# LDP_DS_V2_0.net
KiCad netlist of a schematic drawn in Altium Designer
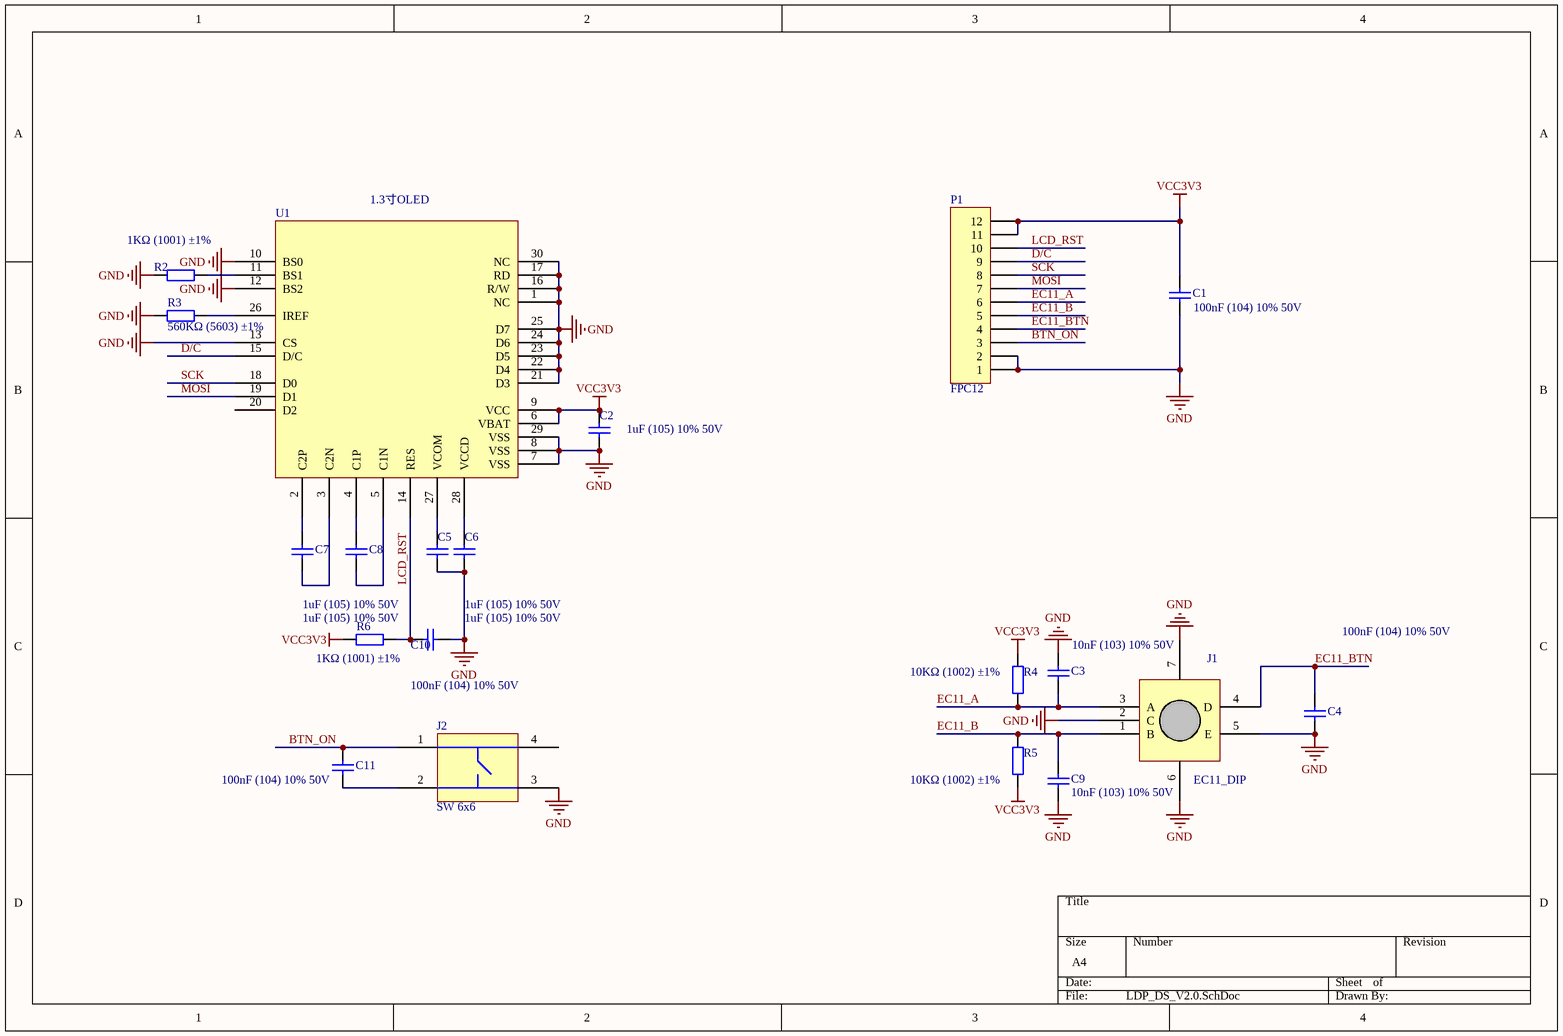
[diagram p0: LDP_DS_V2.0.SchDoc]

(export (version "E")
  (design (tool "Eeschema 10.0.6"))
  (components
    (comp (ref "C1")
      (value "100nF (104) 10% 50V")
      (footprint "0603_C")
      (description "贴片电容")
      (libsource (lib "Cap") (part "0603 100nF (104) 10% 50V"))
    )
    (comp (ref "C2")
      (value "1uF (105) 10% 50V")
      (footprint "0603_C")
      (description "贴片电容")
      (libsource (lib "Cap") (part "0603 1uF (105) 10% 50V"))
    )
    (comp (ref "C3")
      (value "10nF (103) 10% 50V")
      (footprint "0603_C")
      (description "贴片电容")
      (libsource (lib "Cap") (part "0603 10nF (103) 10% 50V"))
    )
    (comp (ref "C4")
      (value "100nF (104) 10% 50V")
      (footprint "0603_C")
      (description "贴片电容")
      (libsource (lib "Cap") (part "0603 100nF (104) 10% 50V"))
    )
    (comp (ref "C5")
      (value "1uF (105) 10% 50V")
      (footprint "0603_C")
      (description "贴片电容")
      (libsource (lib "Cap") (part "0603 1uF (105) 10% 50V"))
    )
    (comp (ref "C6")
      (value "1uF (105) 10% 50V")
      (footprint "0603_C")
      (description "贴片电容")
      (libsource (lib "Cap") (part "0603 1uF (105) 10% 50V"))
    )
    (comp (ref "C7")
      (value "1uF (105) 10% 50V")
      (footprint "0603_C")
      (description "贴片电容")
      (libsource (lib "Cap") (part "0603 1uF (105) 10% 50V"))
    )
    (comp (ref "C8")
      (value "1uF (105) 10% 50V")
      (footprint "0603_C")
      (description "贴片电容")
      (libsource (lib "Cap") (part "0603 1uF (105) 10% 50V"))
    )
    (comp (ref "C9")
      (value "10nF (103) 10% 50V")
      (footprint "0603_C")
      (description "贴片电容")
      (libsource (lib "Cap") (part "0603 10nF (103) 10% 50V"))
    )
    (comp (ref "C10")
      (value "100nF (104) 10% 50V")
      (footprint "0603_C")
      (description "贴片电容")
      (libsource (lib "Cap") (part "0603 100nF (104) 10% 50V"))
    )
    (comp (ref "C11")
      (value "100nF (104) 10% 50V")
      (footprint "0603_C")
      (description "贴片电容")
      (libsource (lib "Cap") (part "0603 100nF (104) 10% 50V"))
    )
    (comp (ref "J1") (value "EC11_DIP") (footprint "EC11_DIP") (libsource (lib "CONNECT") (part "EC11_DIP")))
    (comp (ref "J2") (value "SW 6x6") (footprint "SW 6x6") (libsource (lib "CONNECT") (part "SW 6x6")))
    (comp (ref "P1")
      (value "FPC12")
      (footprint "FPC_12")
      (description "Header, 12-Pin")
      (fields (field (name "PUBLISHER") "Altium Limited"))
      (libsource (lib "Miscellaneous Connectors") (part "Header 12"))
    )
    (comp (ref "R2")
      (value "1KΩ (1001) ±1%")
      (footprint "0603_R")
      (description "贴片电阻")
      (libsource (lib "RES") (part "0603 1KΩ (1001) 1%"))
    )
    (comp (ref "R3")
      (value "560KΩ (5603) ±1%")
      (footprint "0603_R")
      (description "贴片电阻")
      (libsource (lib "RES") (part "0603 560KΩ (5603) 1%"))
    )
    (comp (ref "R4")
      (value "10KΩ (1002) ±1%")
      (footprint "0603_R")
      (description "贴片电阻")
      (libsource (lib "RES") (part "0603 10KΩ (1002) 1%"))
    )
    (comp (ref "R5")
      (value "10KΩ (1002) ±1%")
      (footprint "0603_R")
      (description "贴片电阻")
      (libsource (lib "RES") (part "0603 10KΩ (1002) 1%"))
    )
    (comp (ref "R6")
      (value "1KΩ (1001) ±1%")
      (footprint "0603_R")
      (description "贴片电阻")
      (libsource (lib "RES") (part "0603 1KΩ (1001) 1%"))
    )
    (comp (ref "U1") (value "1.3寸OLED") (footprint "1.3寸OLED") (libsource (lib "LED") (part "1.3寸OLED")))
  )
  (nets
    (net (code "1") (name "/BTN_ON") (class "Default")
      (node (ref "C11") (pin "2") (pinfunction "2_2") (pintype "passive"))
      (node (ref "J2") (pin "1") (pintype "passive"))
      (node (ref "P1") (pin "3") (pinfunction "3_3") (pintype "passive"))
    )
    (net (code "2") (name "/D{slash}C") (class "Default")
      (node (ref "P1") (pin "9") (pinfunction "9_9") (pintype "passive"))
      (node (ref "U1") (pin "15") (pinfunction "D/C_15") (pintype "passive"))
    )
    (net (code "3") (name "/EC11_A") (class "Default")
      (node (ref "C3") (pin "1") (pinfunction "1_1") (pintype "passive"))
      (node (ref "J1") (pin "3") (pinfunction "A_3") (pintype "passive"))
      (node (ref "P1") (pin "6") (pinfunction "6_6") (pintype "passive"))
      (node (ref "R4") (pin "1") (pinfunction "1_1") (pintype "passive"))
    )
    (net (code "4") (name "/EC11_B") (class "Default")
      (node (ref "C9") (pin "2") (pinfunction "2_2") (pintype "passive"))
      (node (ref "J1") (pin "1") (pinfunction "B_1") (pintype "passive"))
      (node (ref "P1") (pin "5") (pinfunction "5_5") (pintype "passive"))
      (node (ref "R5") (pin "2") (pinfunction "2_2") (pintype "passive"))
    )
    (net (code "5") (name "/EC11_BTN") (class "Default")
      (node (ref "C4") (pin "2") (pinfunction "2_2") (pintype "passive"))
      (node (ref "J1") (pin "4") (pinfunction "D_4") (pintype "passive"))
      (node (ref "P1") (pin "4") (pinfunction "4_4") (pintype "passive"))
    )
    (net (code "6") (name "/LCD_RST") (class "Default")
      (node (ref "C10") (pin "1") (pinfunction "1_1") (pintype "passive"))
      (node (ref "P1") (pin "10") (pinfunction "10_10") (pintype "passive"))
      (node (ref "R6") (pin "1") (pinfunction "1_1") (pintype "passive"))
      (node (ref "U1") (pin "14") (pinfunction "RES_14") (pintype "passive"))
    )
    (net (code "7") (name "/MOSI") (class "Default")
      (node (ref "P1") (pin "7") (pinfunction "7_7") (pintype "passive"))
      (node (ref "U1") (pin "19") (pinfunction "D1_19") (pintype "passive"))
    )
    (net (code "8") (name "/SCK") (class "Default")
      (node (ref "P1") (pin "8") (pinfunction "8_8") (pintype "passive"))
      (node (ref "U1") (pin "18") (pinfunction "D0_18") (pintype "passive"))
    )
    (net (code "9") (name "GND") (class "Default")
      (node (ref "C1") (pin "1") (pinfunction "1_1") (pintype "passive"))
      (node (ref "C10") (pin "2") (pinfunction "2_2") (pintype "passive"))
      (node (ref "C2") (pin "1") (pinfunction "1_1") (pintype "passive"))
      (node (ref "C3") (pin "2") (pinfunction "2_2") (pintype "passive"))
      (node (ref "C4") (pin "1") (pinfunction "1_1") (pintype "passive"))
      (node (ref "C5") (pin "1") (pinfunction "1_1") (pintype "passive"))
      (node (ref "C6") (pin "1") (pinfunction "1_1") (pintype "passive"))
      (node (ref "C9") (pin "1") (pinfunction "1_1") (pintype "passive"))
      (node (ref "J1") (pin "2") (pinfunction "C_2") (pintype "passive"))
      (node (ref "J1") (pin "5") (pinfunction "E_5") (pintype "passive"))
      (node (ref "J1") (pin "6") (pintype "passive"))
      (node (ref "J1") (pin "7") (pintype "passive"))
      (node (ref "J2") (pin "3") (pintype "passive"))
      (node (ref "P1") (pin "1") (pinfunction "1_1") (pintype "passive"))
      (node (ref "P1") (pin "2") (pinfunction "2_2") (pintype "passive"))
      (node (ref "R2") (pin "2") (pinfunction "2_2") (pintype "passive"))
      (node (ref "R3") (pin "1") (pinfunction "1_1") (pintype "passive"))
      (node (ref "U1") (pin "1") (pinfunction "NC_1") (pintype "passive"))
      (node (ref "U1") (pin "10") (pinfunction "BS0_10") (pintype "passive"))
      (node (ref "U1") (pin "12") (pinfunction "BS2_12") (pintype "passive"))
      (node (ref "U1") (pin "13") (pinfunction "CS_13") (pintype "passive"))
      (node (ref "U1") (pin "16") (pinfunction "R/W_16") (pintype "passive"))
      (node (ref "U1") (pin "17") (pinfunction "RD_17") (pintype "passive"))
      (node (ref "U1") (pin "21") (pinfunction "D3_21") (pintype "passive"))
      (node (ref "U1") (pin "22") (pinfunction "D4_22") (pintype "passive"))
      (node (ref "U1") (pin "23") (pinfunction "D5_23") (pintype "passive"))
      (node (ref "U1") (pin "24") (pinfunction "D6_24") (pintype "passive"))
      (node (ref "U1") (pin "25") (pinfunction "D7_25") (pintype "passive"))
      (node (ref "U1") (pin "29") (pinfunction "VSS_29") (pintype "passive"))
      (node (ref "U1") (pin "30") (pinfunction "NC_30") (pintype "passive"))
      (node (ref "U1") (pin "7") (pinfunction "VSS_7") (pintype "passive"))
      (node (ref "U1") (pin "8") (pinfunction "VSS_8") (pintype "passive"))
    )
    (net (code "10") (name "Net-(C11-Pad1)") (class "Default")
      (node (ref "C11") (pin "1") (pinfunction "1_1") (pintype "passive"))
      (node (ref "J2") (pin "2") (pintype "passive"))
    )
    (net (code "11") (name "Net-(U1-BS1)") (class "Default")
      (node (ref "R2") (pin "1") (pinfunction "1_1") (pintype "passive"))
      (node (ref "U1") (pin "11") (pinfunction "BS1_11") (pintype "passive"))
    )
    (net (code "12") (name "Net-(U1-C1N)") (class "Default")
      (node (ref "C8") (pin "1") (pinfunction "1_1") (pintype "passive"))
      (node (ref "U1") (pin "5") (pinfunction "C1N_5") (pintype "passive"))
    )
    (net (code "13") (name "Net-(U1-C1P)") (class "Default")
      (node (ref "C8") (pin "2") (pinfunction "2_2") (pintype "passive"))
      (node (ref "U1") (pin "4") (pinfunction "C1P_4") (pintype "passive"))
    )
    (net (code "14") (name "Net-(U1-C2N)") (class "Default")
      (node (ref "C7") (pin "1") (pinfunction "1_1") (pintype "passive"))
      (node (ref "U1") (pin "3") (pinfunction "C2N_3") (pintype "passive"))
    )
    (net (code "15") (name "Net-(U1-C2P)") (class "Default")
      (node (ref "C7") (pin "2") (pinfunction "2_2") (pintype "passive"))
      (node (ref "U1") (pin "2") (pinfunction "C2P_2") (pintype "passive"))
    )
    (net (code "16") (name "Net-(U1-IREF)") (class "Default")
      (node (ref "R3") (pin "2") (pinfunction "2_2") (pintype "passive"))
      (node (ref "U1") (pin "26") (pinfunction "IREF_26") (pintype "passive"))
    )
    (net (code "17") (name "Net-(U1-VCCD)") (class "Default")
      (node (ref "C6") (pin "2") (pinfunction "2_2") (pintype "passive"))
      (node (ref "U1") (pin "28") (pinfunction "VCCD_28") (pintype "passive"))
    )
    (net (code "18") (name "Net-(U1-VCOM)") (class "Default")
      (node (ref "C5") (pin "2") (pinfunction "2_2") (pintype "passive"))
      (node (ref "U1") (pin "27") (pinfunction "VCOM_27") (pintype "passive"))
    )
    (net (code "19") (name "VCC3V3") (class "Default")
      (node (ref "C1") (pin "2") (pinfunction "2_2") (pintype "passive"))
      (node (ref "C2") (pin "2") (pinfunction "2_2") (pintype "passive"))
      (node (ref "P1") (pin "11") (pinfunction "11_11") (pintype "passive"))
      (node (ref "P1") (pin "12") (pinfunction "12_12") (pintype "passive"))
      (node (ref "R4") (pin "2") (pinfunction "2_2") (pintype "passive"))
      (node (ref "R5") (pin "1") (pinfunction "1_1") (pintype "passive"))
      (node (ref "R6") (pin "2") (pinfunction "2_2") (pintype "passive"))
      (node (ref "U1") (pin "6") (pinfunction "VBAT_6") (pintype "passive"))
      (node (ref "U1") (pin "9") (pinfunction "VCC_9") (pintype "passive"))
    )
    (net (code "20") (name "unconnected-(J2-Pad4)") (class "Default")
      (node (ref "J2") (pin "4") (pintype "passive"))
    )
    (net (code "21") (name "unconnected-(U1-D2-Pad20)") (class "Default")
      (node (ref "U1") (pin "20") (pinfunction "D2_20") (pintype "passive"))
    )
  )
)
